# PRA_2_5_23_1.net
KiCad netlist of a schematic drawn in EAGLE
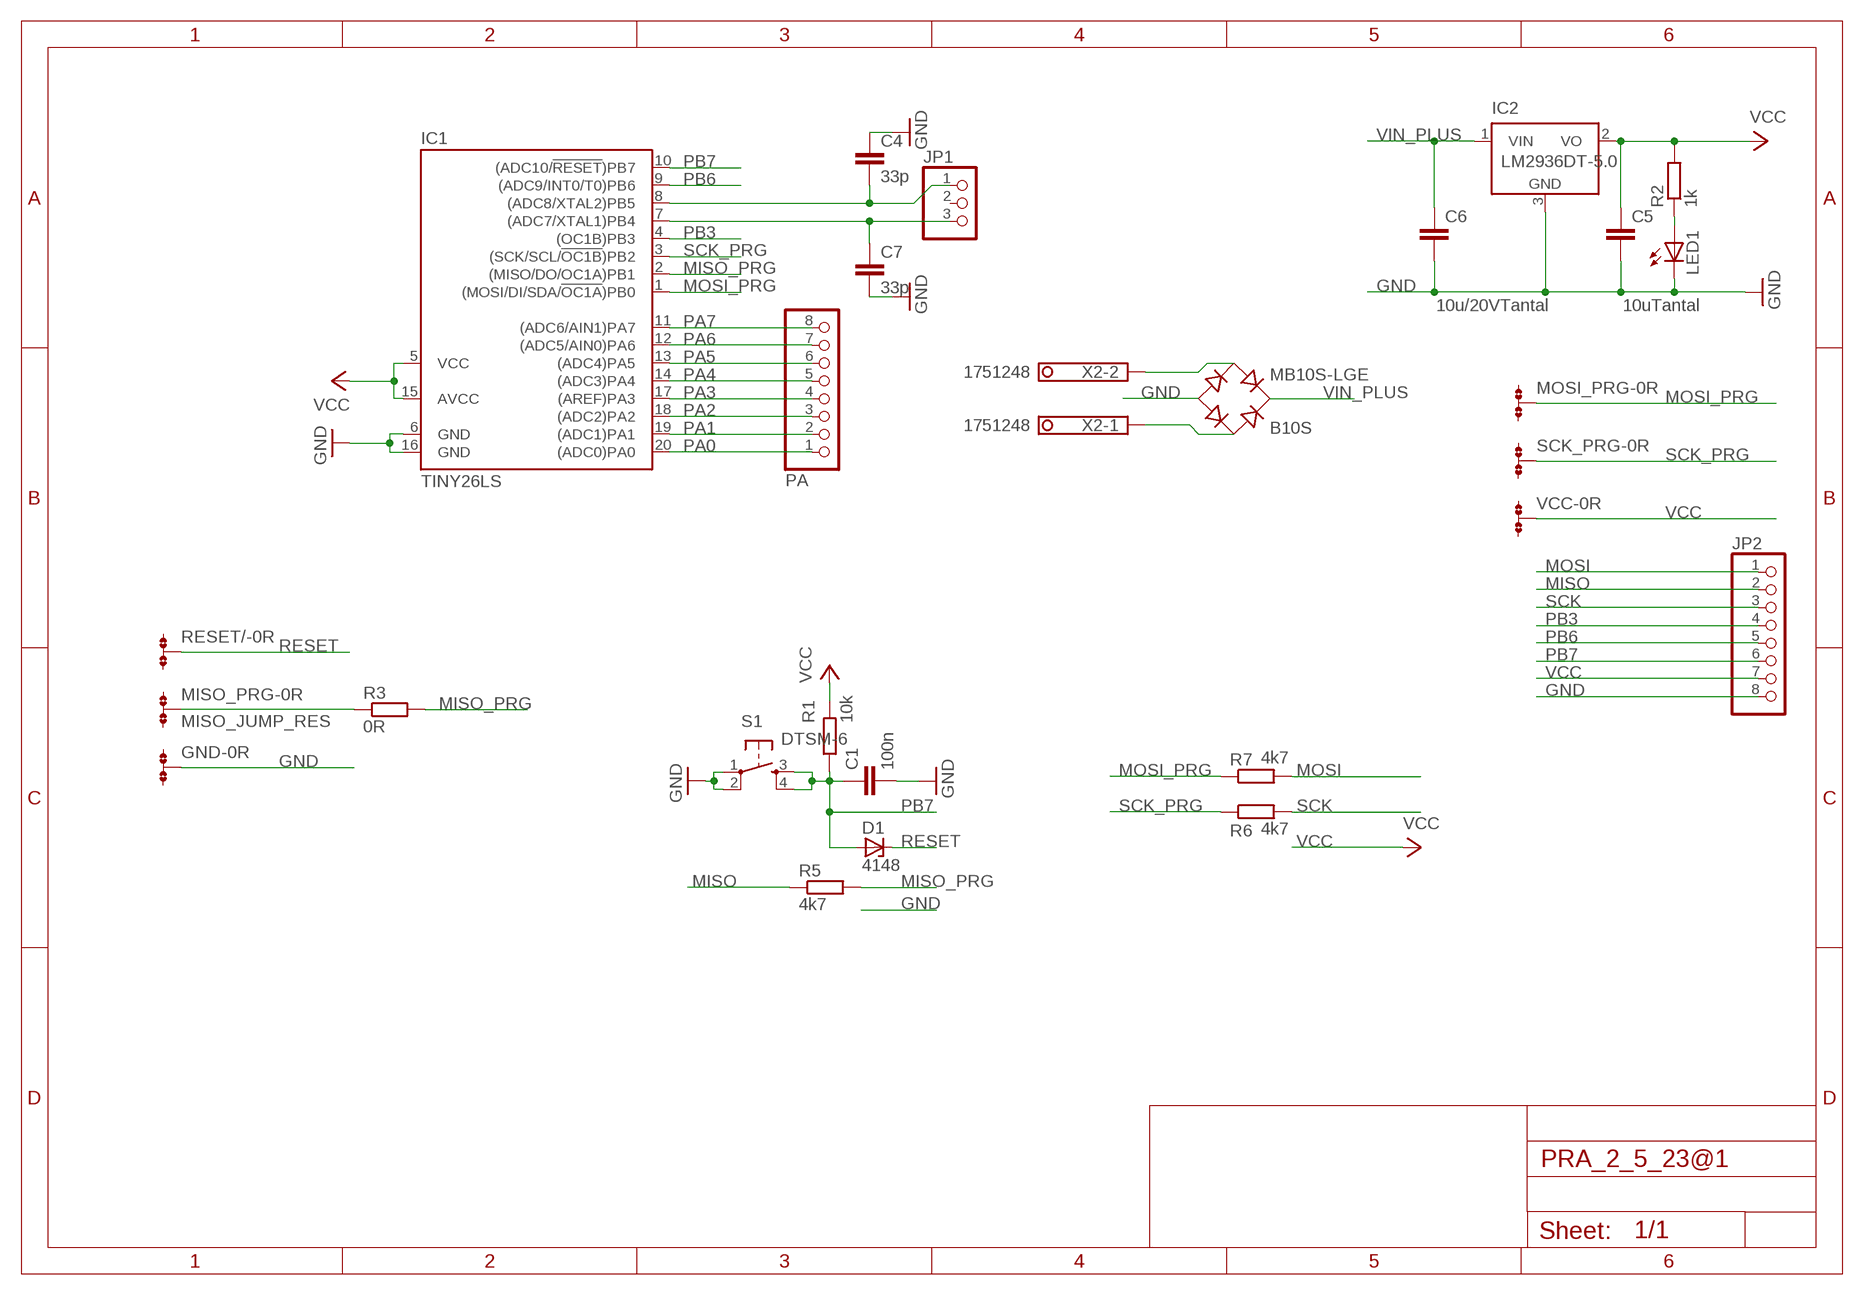
[diagram p0: schematic, sheet 1]

(export (version "E")
  (design (tool "Eeschema 10.0.6"))
  (components
    (comp (ref "C1")
      (value "100n")
      (footprint "eagle-import:C1206")
      (libsource (lib "eagle-import") (part "C-EUC1206"))
    )
    (comp (ref "C4")
      (value "33p")
      (footprint "eagle-import:C1206")
      (libsource (lib "eagle-import") (part "C-EUC1206"))
    )
    (comp (ref "C5")
      (value "10uTantal")
      (footprint "eagle-import:C1206K")
      (libsource (lib "eagle-import") (part "C-EUC1206K"))
    )
    (comp (ref "C6")
      (value "10u/20VTantal")
      (footprint "eagle-import:C1206K")
      (libsource (lib "eagle-import") (part "C-EUC1206K"))
    )
    (comp (ref "C7")
      (value "33p")
      (footprint "eagle-import:C1206")
      (libsource (lib "eagle-import") (part "C-EUC1206"))
    )
    (comp (ref "D1")
      (value "4148")
      (footprint "eagle-import:SMB")
      (libsource (lib "eagle-import") (part "ZENER-DIODESMB"))
    )
    (comp (ref "GND")
      (value "0R-JUMPA")
      (footprint "eagle-import:A0R-JMP")
      (libsource (lib "eagle-import") (part "0R-JUMPA"))
    )
    (comp (ref "IC1")
      (value "TINY26LS")
      (footprint "eagle-import:SO20L")
      (fields (field (name "MPN") "ATTINY26L-8SU"))
      (libsource (lib "eagle-import") (part "TINY26SL"))
    )
    (comp (ref "IC2")
      (value "LM2936DT-5.0")
      (footprint "eagle-import:TO252")
      (fields (field (name "MF") "NATIONAL SEMICONDUCTOR") (field (name "MPN") "LM2936DT-5.0/NOPB"))
      (libsource (lib "eagle-import") (part "LM2936?DT-5.0"))
    )
    (comp (ref "JP1")
      (value "PINHD-1X3")
      (footprint "eagle-import:1X03")
      (libsource (lib "eagle-import") (part "PINHD-1X3"))
    )
    (comp (ref "JP2")
      (value "PINHD-1X8/90")
      (footprint "eagle-import:1X08_90")
      (libsource (lib "eagle-import") (part "PINHD-1X8/90"))
    )
    (comp (ref "LED1")
      (value "LEDSMT1206")
      (footprint "eagle-import:1206")
      (libsource (lib "eagle-import") (part "LEDSMT1206"))
    )
    (comp (ref "MB10S-LGE")
      (value "B10S")
      (footprint "eagle-import:MBS")
      (libsource (lib "eagle-import") (part "BS10"))
    )
    (comp (ref "MISO_PRG")
      (value "0R-JUMPA")
      (footprint "eagle-import:A0R-JMP")
      (libsource (lib "eagle-import") (part "0R-JUMPA"))
    )
    (comp (ref "MOSI_PRG")
      (value "0R-JUMPA")
      (footprint "eagle-import:A0R-JMP")
      (libsource (lib "eagle-import") (part "0R-JUMPA"))
    )
    (comp (ref "PA")
      (value "PINHD-1X8/90")
      (footprint "eagle-import:1X08_90")
      (libsource (lib "eagle-import") (part "PINHD-1X8/90"))
    )
    (comp (ref "R1")
      (value "10k")
      (footprint "eagle-import:R1206")
      (libsource (lib "eagle-import") (part "R-EU_R1206"))
    )
    (comp (ref "R2")
      (value "1k")
      (footprint "eagle-import:R1206")
      (libsource (lib "eagle-import") (part "R-EU_R1206"))
    )
    (comp (ref "R3")
      (value "0R")
      (footprint "eagle-import:M1406")
      (libsource (lib "eagle-import") (part "R-EU_M1406"))
    )
    (comp (ref "R5")
      (value "4k7")
      (footprint "eagle-import:R1206")
      (libsource (lib "eagle-import") (part "R-EU_R1206"))
    )
    (comp (ref "R6")
      (value "4k7")
      (footprint "eagle-import:R1206")
      (libsource (lib "eagle-import") (part "R-EU_R1206"))
    )
    (comp (ref "R7")
      (value "4k7")
      (footprint "eagle-import:R1206")
      (libsource (lib "eagle-import") (part "R-EU_R1206"))
    )
    (comp (ref "RESET/")
      (value "0R-JUMPA")
      (footprint "eagle-import:A0R-JMP")
      (libsource (lib "eagle-import") (part "0R-JUMPA"))
    )
    (comp (ref "S1")
      (value "DTSM-6")
      (footprint "eagle-import:DTSM-6")
      (libsource (lib "eagle-import") (part "DTSM-6"))
    )
    (comp (ref "SCK_PRG")
      (value "0R-JUMPA")
      (footprint "eagle-import:A0R-JMP")
      (libsource (lib "eagle-import") (part "0R-JUMPA"))
    )
    (comp (ref "VCC")
      (value "0R-JUMPA")
      (footprint "eagle-import:A0R-JMP")
      (libsource (lib "eagle-import") (part "0R-JUMPA"))
    )
    (comp (ref "X2")
      (value "1751248")
      (footprint "eagle-import:1751248")
      (libsource (lib "eagle-import") (part "1751248"))
    )
  )
  (nets
    (net (code "1") (name "/MISO") (class "Default")
      (node (ref "JP2") (pin "2") (pinfunction "2_2") (pintype "passive"))
      (node (ref "R5") (pin "1") (pinfunction "1_1") (pintype "passive"))
    )
    (net (code "2") (name "/MISO_JUMP_RES") (class "Default")
      (node (ref "MISO_PRG") (pin "2") (pinfunction "2_2") (pintype "passive"))
      (node (ref "R3") (pin "1") (pinfunction "1_1") (pintype "passive"))
    )
    (net (code "3") (name "/MISO_PRG") (class "Default")
      (node (ref "IC1") (pin "2") (pinfunction "(MISO/DO/OC1A)PB1_2") (pintype "bidirectional"))
      (node (ref "R3") (pin "2") (pinfunction "2_2") (pintype "passive"))
      (node (ref "R5") (pin "2") (pinfunction "2_2") (pintype "passive"))
    )
    (net (code "4") (name "/MOSI") (class "Default")
      (node (ref "JP2") (pin "1") (pinfunction "1_1") (pintype "passive"))
      (node (ref "R7") (pin "2") (pinfunction "2_2") (pintype "passive"))
    )
    (net (code "5") (name "/MOSI_PRG") (class "Default")
      (node (ref "IC1") (pin "1") (pinfunction "(MOSI/DI/SDA/~{OC1A})PB0_1") (pintype "bidirectional"))
      (node (ref "MOSI_PRG") (pin "2") (pinfunction "2_2") (pintype "passive"))
      (node (ref "R7") (pin "1") (pinfunction "1_1") (pintype "passive"))
    )
    (net (code "6") (name "/PA0") (class "Default")
      (node (ref "IC1") (pin "20") (pinfunction "(ADC0)PA0_20") (pintype "bidirectional"))
      (node (ref "PA") (pin "1") (pinfunction "1_1") (pintype "passive"))
    )
    (net (code "7") (name "/PA1") (class "Default")
      (node (ref "IC1") (pin "19") (pinfunction "(ADC1)PA1_19") (pintype "bidirectional"))
      (node (ref "PA") (pin "2") (pinfunction "2_2") (pintype "passive"))
    )
    (net (code "8") (name "/PA2") (class "Default")
      (node (ref "IC1") (pin "18") (pinfunction "(ADC2)PA2_18") (pintype "bidirectional"))
      (node (ref "PA") (pin "3") (pinfunction "3_3") (pintype "passive"))
    )
    (net (code "9") (name "/PA3") (class "Default")
      (node (ref "IC1") (pin "17") (pinfunction "(AREF)PA3_17") (pintype "bidirectional"))
      (node (ref "PA") (pin "4") (pinfunction "4_4") (pintype "passive"))
    )
    (net (code "10") (name "/PA4") (class "Default")
      (node (ref "IC1") (pin "14") (pinfunction "(ADC3)PA4_14") (pintype "bidirectional"))
      (node (ref "PA") (pin "5") (pinfunction "5_5") (pintype "passive"))
    )
    (net (code "11") (name "/PA5") (class "Default")
      (node (ref "IC1") (pin "13") (pinfunction "(ADC4)PA5_13") (pintype "bidirectional"))
      (node (ref "PA") (pin "6") (pinfunction "6_6") (pintype "passive"))
    )
    (net (code "12") (name "/PA6") (class "Default")
      (node (ref "IC1") (pin "12") (pinfunction "(ADC5/AIN0)PA6_12") (pintype "bidirectional"))
      (node (ref "PA") (pin "7") (pinfunction "7_7") (pintype "passive"))
    )
    (net (code "13") (name "/PA7") (class "Default")
      (node (ref "IC1") (pin "11") (pinfunction "(ADC6/AIN1)PA7_11") (pintype "bidirectional"))
      (node (ref "PA") (pin "8") (pinfunction "8_8") (pintype "passive"))
    )
    (net (code "14") (name "/PB3") (class "Default")
      (node (ref "IC1") (pin "4") (pinfunction "(OC1B)PB3_4") (pintype "bidirectional"))
      (node (ref "JP2") (pin "4") (pinfunction "4_4") (pintype "passive"))
    )
    (net (code "15") (name "/PB6") (class "Default")
      (node (ref "IC1") (pin "9") (pinfunction "(ADC9/INT0/T0)PB6_9") (pintype "bidirectional"))
      (node (ref "JP2") (pin "5") (pinfunction "5_5") (pintype "passive"))
    )
    (net (code "16") (name "/PB7") (class "Default")
      (node (ref "C1") (pin "1") (pinfunction "1_1") (pintype "passive"))
      (node (ref "D1") (pin "A") (pinfunction "A_A") (pintype "passive"))
      (node (ref "IC1") (pin "10") (pinfunction "(ADC10/~{RESET})PB7_10") (pintype "bidirectional"))
      (node (ref "JP2") (pin "6") (pinfunction "6_6") (pintype "passive"))
      (node (ref "R1") (pin "1") (pinfunction "1_1") (pintype "passive"))
      (node (ref "S1") (pin "3") (pinfunction "3_3") (pintype "passive"))
      (node (ref "S1") (pin "4") (pinfunction "4_4") (pintype "passive"))
    )
    (net (code "17") (name "/RESET") (class "Default")
      (node (ref "D1") (pin "C") (pinfunction "C_C") (pintype "passive"))
      (node (ref "RESET/") (pin "2") (pinfunction "2_2") (pintype "passive"))
    )
    (net (code "18") (name "/SCK") (class "Default")
      (node (ref "JP2") (pin "3") (pinfunction "3_3") (pintype "passive"))
      (node (ref "R6") (pin "2") (pinfunction "2_2") (pintype "passive"))
    )
    (net (code "19") (name "/SCK_PRG") (class "Default")
      (node (ref "IC1") (pin "3") (pinfunction "(SCK/SCL/~{OC1B})PB2_3") (pintype "bidirectional"))
      (node (ref "R6") (pin "1") (pinfunction "1_1") (pintype "passive"))
      (node (ref "SCK_PRG") (pin "2") (pinfunction "2_2") (pintype "passive"))
    )
    (net (code "20") (name "/VIN_PLUS") (class "Default")
      (node (ref "C6") (pin "1") (pinfunction "1_1") (pintype "passive"))
      (node (ref "IC2") (pin "1") (pinfunction "VIN_1") (pintype "input"))
      (node (ref "MB10S-LGE") (pin "+") (pinfunction "+_+") (pintype "passive"))
    )
    (net (code "21") (name "GND") (class "Default")
      (node (ref "C1") (pin "2") (pinfunction "2_2") (pintype "passive"))
      (node (ref "C4") (pin "1") (pinfunction "1_1") (pintype "passive"))
      (node (ref "C5") (pin "2") (pinfunction "2_2") (pintype "passive"))
      (node (ref "C6") (pin "2") (pinfunction "2_2") (pintype "passive"))
      (node (ref "C7") (pin "2") (pinfunction "2_2") (pintype "passive"))
      (node (ref "GND") (pin "2") (pinfunction "2_2") (pintype "passive"))
      (node (ref "IC1") (pin "16") (pinfunction "GND_16") (pintype "power_in"))
      (node (ref "IC1") (pin "6") (pinfunction "GND_6") (pintype "power_in"))
      (node (ref "IC2") (pin "3") (pinfunction "GND_3") (pintype "passive"))
      (node (ref "JP2") (pin "8") (pinfunction "8_8") (pintype "passive"))
      (node (ref "LED1") (pin "C") (pinfunction "C_C") (pintype "passive"))
      (node (ref "MB10S-LGE") (pin "-") (pinfunction "-_-") (pintype "passive"))
      (node (ref "S1") (pin "1") (pinfunction "1_1") (pintype "passive"))
      (node (ref "S1") (pin "2") (pinfunction "2_2") (pintype "passive"))
    )
    (net (code "22") (name "Net-(IC1-(ADC7{slash}XTAL1)PB4)") (class "Default")
      (node (ref "C7") (pin "1") (pinfunction "1_1") (pintype "passive"))
      (node (ref "IC1") (pin "7") (pinfunction "(ADC7/XTAL1)PB4_7") (pintype "bidirectional"))
      (node (ref "JP1") (pin "3") (pinfunction "3_3") (pintype "passive"))
    )
    (net (code "23") (name "Net-(IC1-(ADC8{slash}XTAL2)PB5)") (class "Default")
      (node (ref "C4") (pin "2") (pinfunction "2_2") (pintype "passive"))
      (node (ref "IC1") (pin "8") (pinfunction "(ADC8/XTAL2)PB5_8") (pintype "bidirectional"))
      (node (ref "JP1") (pin "1") (pinfunction "1_1") (pintype "passive"))
    )
    (net (code "24") (name "Net-(LED1-PadA)") (class "Default")
      (node (ref "LED1") (pin "A") (pinfunction "A_A") (pintype "passive"))
      (node (ref "R2") (pin "1") (pinfunction "1_1") (pintype "passive"))
    )
    (net (code "25") (name "Net-(X2A-K)") (class "Default")
      (node (ref "MB10S-LGE") (pin "AC2") (pinfunction "AC2_AC2") (pintype "passive"))
      (node (ref "X2") (pin "1") (pinfunction "K_1") (pintype "passive"))
    )
    (net (code "26") (name "Net-(X2B-K)") (class "Default")
      (node (ref "MB10S-LGE") (pin "AC1") (pinfunction "AC1_AC1") (pintype "passive"))
      (node (ref "X2") (pin "2") (pinfunction "K_2") (pintype "passive"))
    )
    (net (code "27") (name "VCC") (class "Default")
      (node (ref "C5") (pin "1") (pinfunction "1_1") (pintype "passive"))
      (node (ref "IC1") (pin "15") (pinfunction "AVCC_15") (pintype "power_in"))
      (node (ref "IC1") (pin "5") (pinfunction "VCC_5") (pintype "power_in"))
      (node (ref "IC2") (pin "2") (pinfunction "VO_2") (pintype "passive"))
      (node (ref "JP2") (pin "7") (pinfunction "7_7") (pintype "passive"))
      (node (ref "R1") (pin "2") (pinfunction "2_2") (pintype "passive"))
      (node (ref "R2") (pin "2") (pinfunction "2_2") (pintype "passive"))
      (node (ref "VCC") (pin "2") (pinfunction "2_2") (pintype "passive"))
    )
    (net (code "28") (name "unconnected-(GND-Pad1)") (class "Default")
      (node (ref "GND") (pin "1") (pinfunction "1_1") (pintype "passive"))
    )
    (net (code "29") (name "unconnected-(GND-Pad3)") (class "Default")
      (node (ref "GND") (pin "3") (pinfunction "3_3") (pintype "passive"))
    )
    (net (code "30") (name "unconnected-(JP1-Pad2)") (class "Default")
      (node (ref "JP1") (pin "2") (pinfunction "2_2") (pintype "passive"))
    )
    (net (code "31") (name "unconnected-(MISO_PRG-Pad1)") (class "Default")
      (node (ref "MISO_PRG") (pin "1") (pinfunction "1_1") (pintype "passive"))
    )
    (net (code "32") (name "unconnected-(MISO_PRG-Pad3)") (class "Default")
      (node (ref "MISO_PRG") (pin "3") (pinfunction "3_3") (pintype "passive"))
    )
    (net (code "33") (name "unconnected-(MOSI_PRG-Pad1)") (class "Default")
      (node (ref "MOSI_PRG") (pin "1") (pinfunction "1_1") (pintype "passive"))
    )
    (net (code "34") (name "unconnected-(MOSI_PRG-Pad3)") (class "Default")
      (node (ref "MOSI_PRG") (pin "3") (pinfunction "3_3") (pintype "passive"))
    )
    (net (code "35") (name "unconnected-(RESET/-Pad1)") (class "Default")
      (node (ref "RESET/") (pin "1") (pinfunction "1_1") (pintype "passive"))
    )
    (net (code "36") (name "unconnected-(RESET/-Pad3)") (class "Default")
      (node (ref "RESET/") (pin "3") (pinfunction "3_3") (pintype "passive"))
    )
    (net (code "37") (name "unconnected-(SCK_PRG-Pad1)") (class "Default")
      (node (ref "SCK_PRG") (pin "1") (pinfunction "1_1") (pintype "passive"))
    )
    (net (code "38") (name "unconnected-(SCK_PRG-Pad3)") (class "Default")
      (node (ref "SCK_PRG") (pin "3") (pinfunction "3_3") (pintype "passive"))
    )
    (net (code "39") (name "unconnected-(VCC-Pad1)") (class "Default")
      (node (ref "VCC") (pin "1") (pinfunction "1_1") (pintype "passive"))
    )
    (net (code "40") (name "unconnected-(VCC-Pad3)") (class "Default")
      (node (ref "VCC") (pin "3") (pinfunction "3_3") (pintype "passive"))
    )
  )
)
